# Electrical.net
KiCad netlist of a schematic drawn in EAGLE
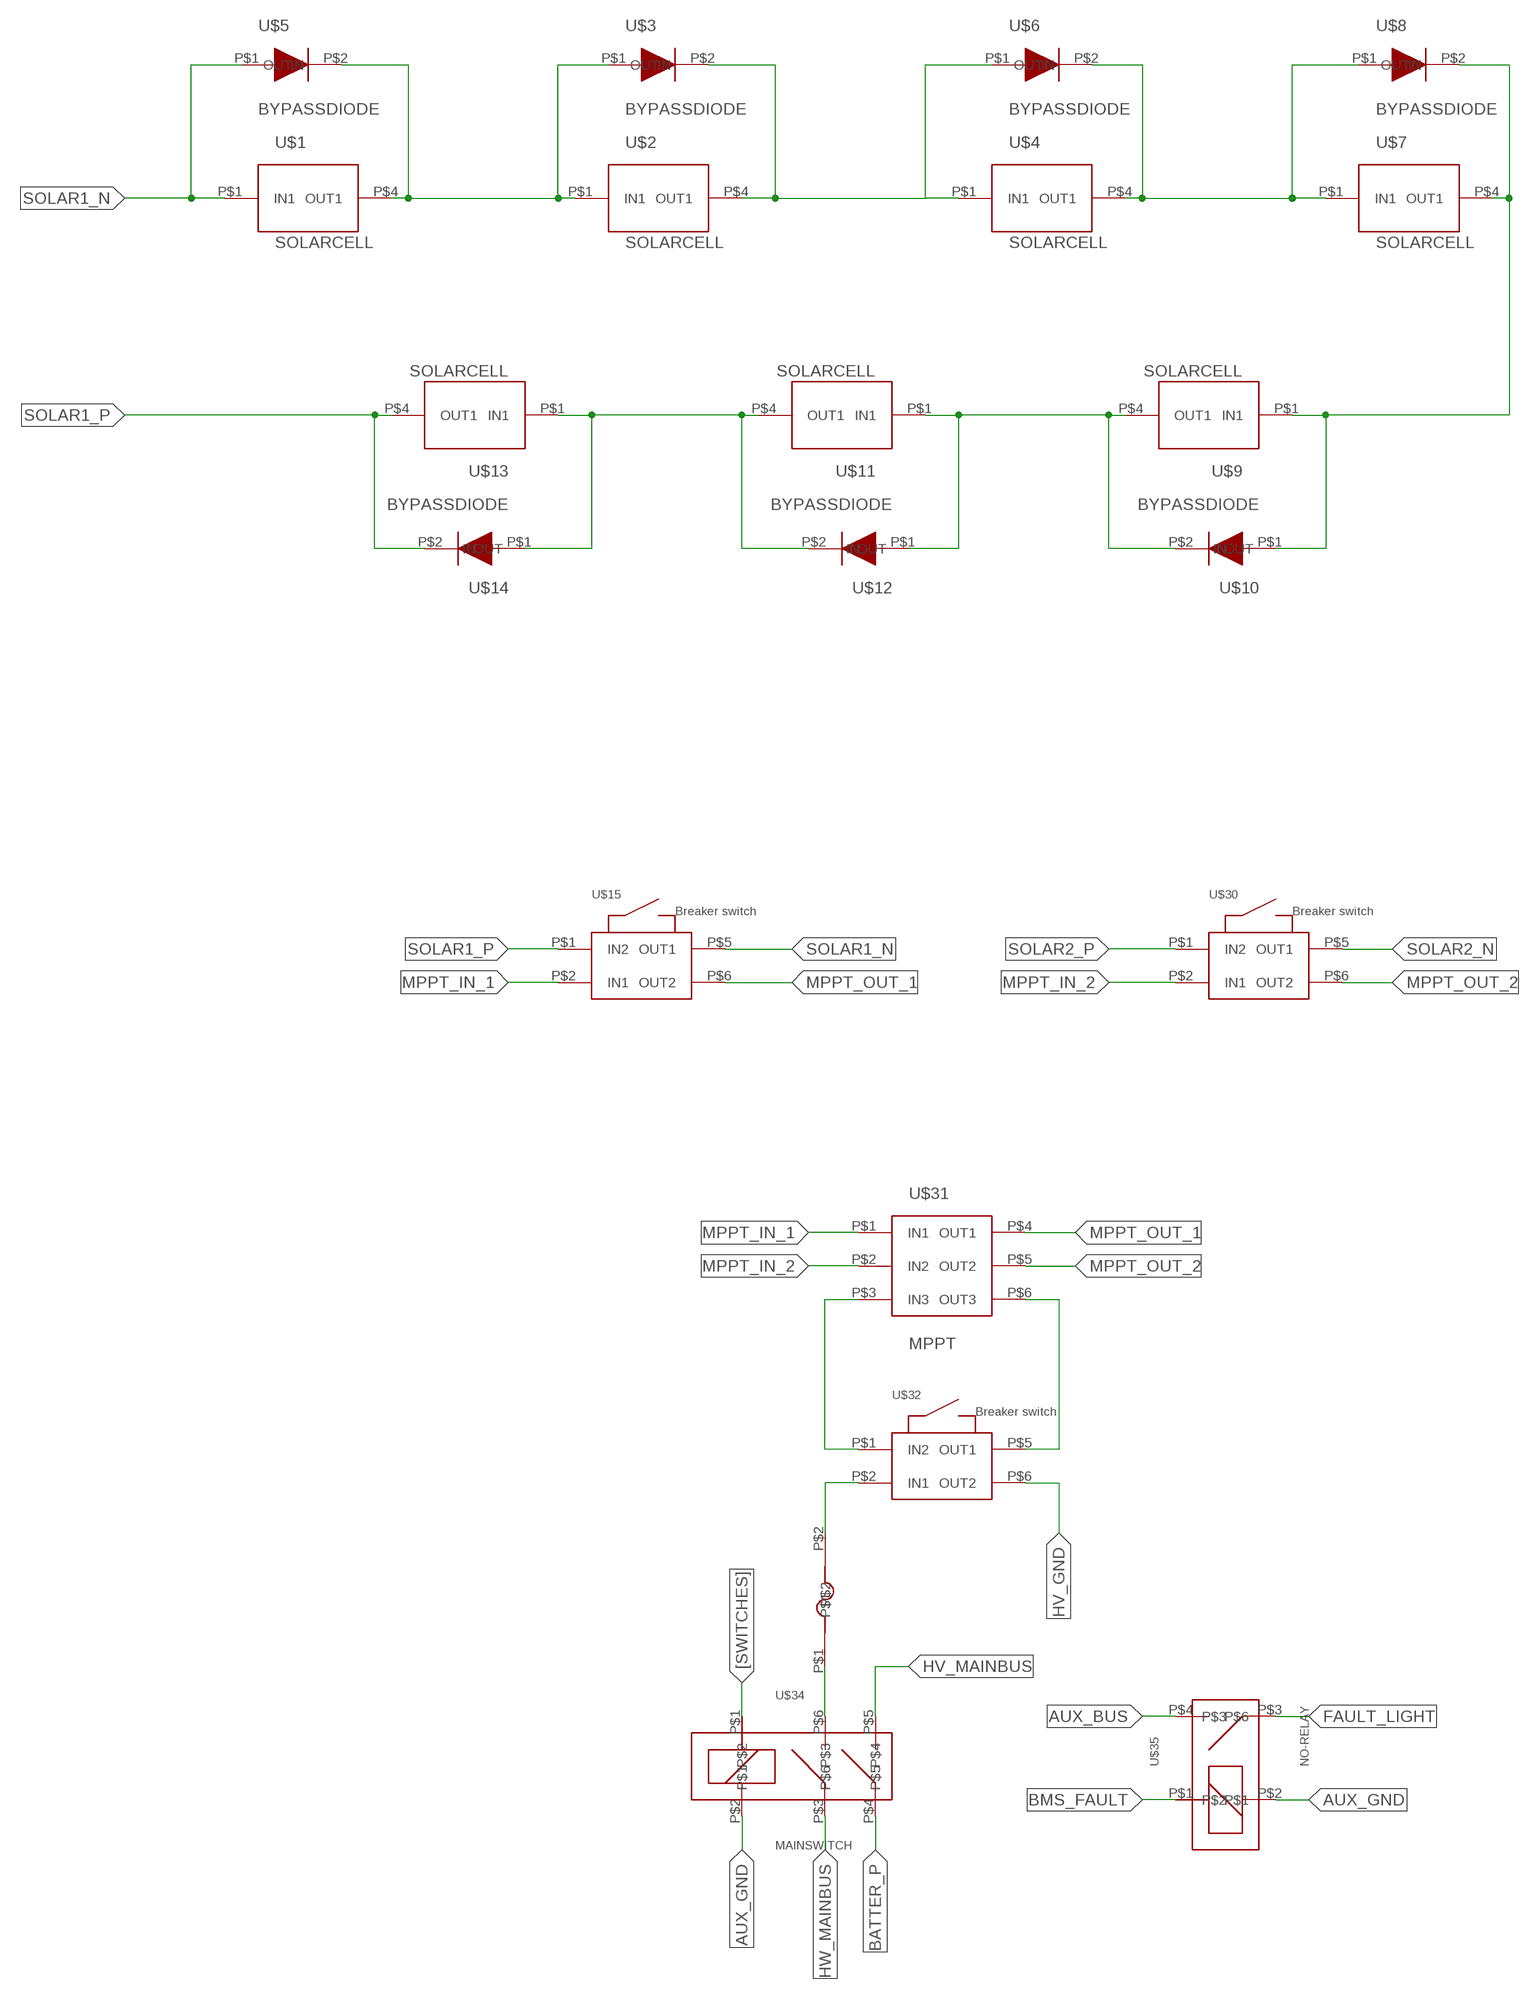
[diagram p0: schematic, sheet 1, part 1 of 3]
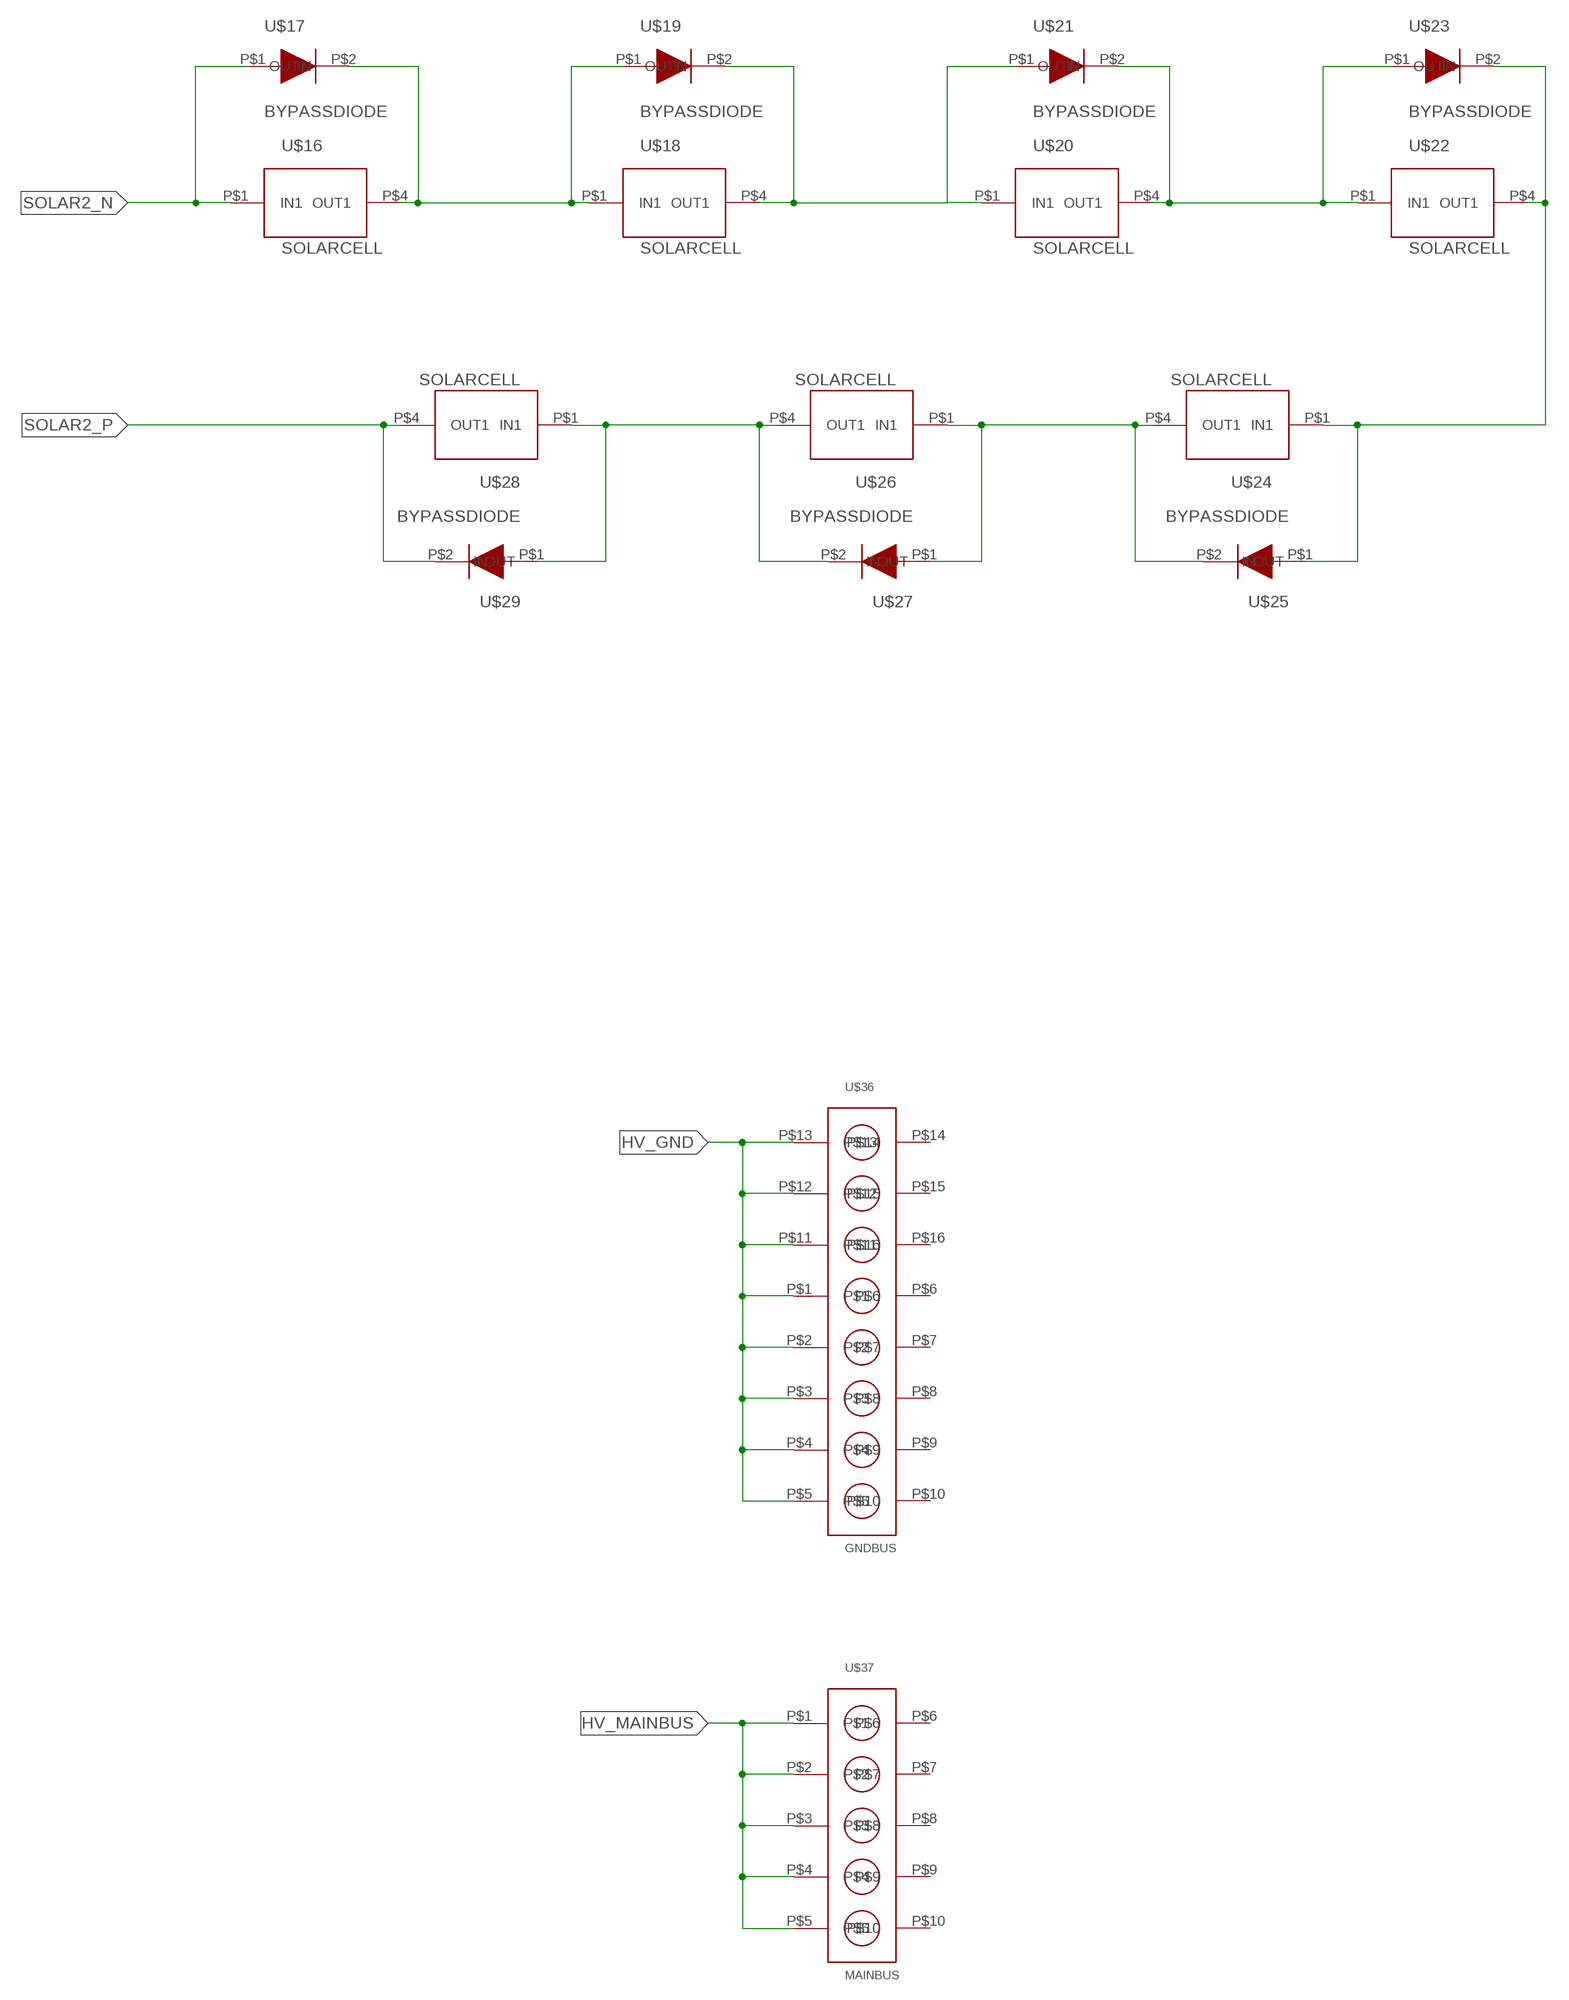
[diagram p1: schematic, sheet 1, part 2 of 3]
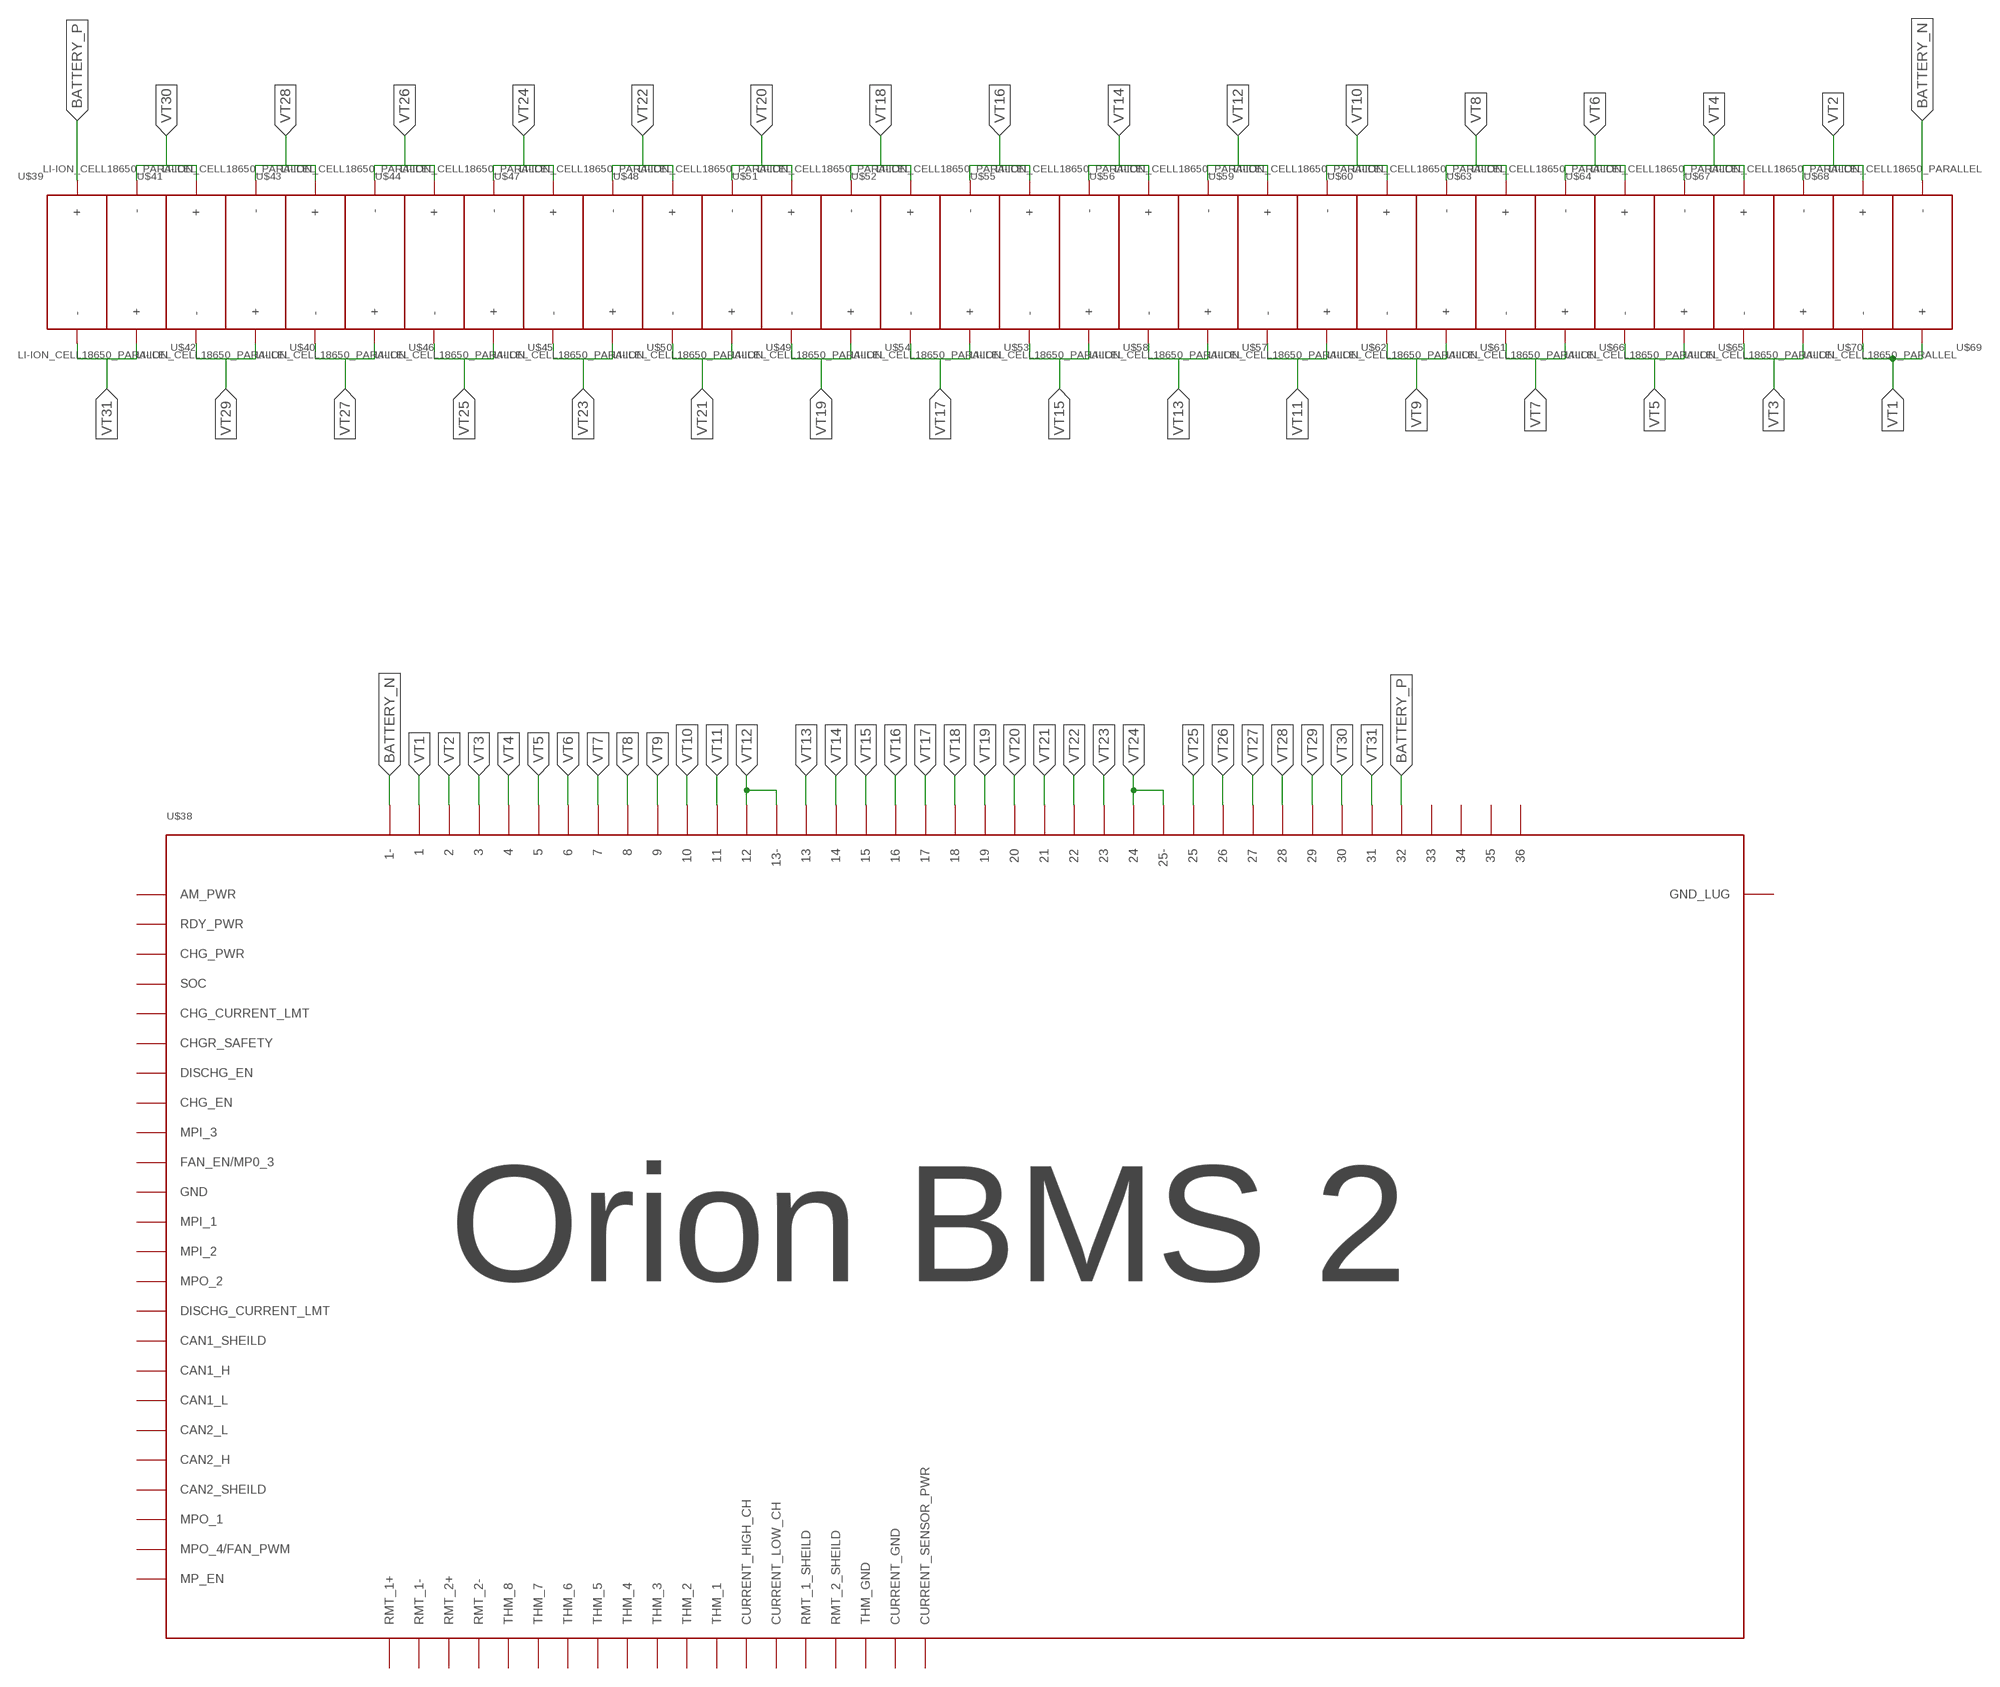
[diagram p2: schematic, sheet 1, part 3 of 3]

(export (version "E")
  (design (tool "Eeschema 10.0.6"))
  (components
    (comp (ref "U$1")
      (value "SOLARCELL")
      (footprint "eagle-import:SOLARCELL")
      (libsource (lib "eagle-import") (part "SOLARCELL"))
    )
    (comp (ref "U$2")
      (value "SOLARCELL")
      (footprint "eagle-import:SOLARCELL")
      (libsource (lib "eagle-import") (part "SOLARCELL"))
    )
    (comp (ref "U$3")
      (value "BYPASSDIODE")
      (footprint "eagle-import:BYPASSDIODE")
      (libsource (lib "eagle-import") (part "BYPASSDIODE"))
    )
    (comp (ref "U$4")
      (value "SOLARCELL")
      (footprint "eagle-import:SOLARCELL")
      (libsource (lib "eagle-import") (part "SOLARCELL"))
    )
    (comp (ref "U$5")
      (value "BYPASSDIODE")
      (footprint "eagle-import:BYPASSDIODE")
      (libsource (lib "eagle-import") (part "BYPASSDIODE"))
    )
    (comp (ref "U$6")
      (value "BYPASSDIODE")
      (footprint "eagle-import:BYPASSDIODE")
      (libsource (lib "eagle-import") (part "BYPASSDIODE"))
    )
    (comp (ref "U$7")
      (value "SOLARCELL")
      (footprint "eagle-import:SOLARCELL")
      (libsource (lib "eagle-import") (part "SOLARCELL"))
    )
    (comp (ref "U$8")
      (value "BYPASSDIODE")
      (footprint "eagle-import:BYPASSDIODE")
      (libsource (lib "eagle-import") (part "BYPASSDIODE"))
    )
    (comp (ref "U$9")
      (value "SOLARCELL")
      (footprint "eagle-import:SOLARCELL")
      (libsource (lib "eagle-import") (part "SOLARCELL"))
    )
    (comp (ref "U$10")
      (value "BYPASSDIODE")
      (footprint "eagle-import:BYPASSDIODE")
      (libsource (lib "eagle-import") (part "BYPASSDIODE"))
    )
    (comp (ref "U$11")
      (value "SOLARCELL")
      (footprint "eagle-import:SOLARCELL")
      (libsource (lib "eagle-import") (part "SOLARCELL"))
    )
    (comp (ref "U$12")
      (value "BYPASSDIODE")
      (footprint "eagle-import:BYPASSDIODE")
      (libsource (lib "eagle-import") (part "BYPASSDIODE"))
    )
    (comp (ref "U$13")
      (value "SOLARCELL")
      (footprint "eagle-import:SOLARCELL")
      (libsource (lib "eagle-import") (part "SOLARCELL"))
    )
    (comp (ref "U$14")
      (value "BYPASSDIODE")
      (footprint "eagle-import:BYPASSDIODE")
      (libsource (lib "eagle-import") (part "BYPASSDIODE"))
    )
    (comp (ref "U$15")
      (value "CIRCUITBREAKER")
      (footprint "eagle-import:CIRUITBREAKER")
      (libsource (lib "eagle-import") (part "CIRCUITBREAKER"))
    )
    (comp (ref "U$16")
      (value "SOLARCELL")
      (footprint "eagle-import:SOLARCELL")
      (libsource (lib "eagle-import") (part "SOLARCELL"))
    )
    (comp (ref "U$17")
      (value "BYPASSDIODE")
      (footprint "eagle-import:BYPASSDIODE")
      (libsource (lib "eagle-import") (part "BYPASSDIODE"))
    )
    (comp (ref "U$18")
      (value "SOLARCELL")
      (footprint "eagle-import:SOLARCELL")
      (libsource (lib "eagle-import") (part "SOLARCELL"))
    )
    (comp (ref "U$19")
      (value "BYPASSDIODE")
      (footprint "eagle-import:BYPASSDIODE")
      (libsource (lib "eagle-import") (part "BYPASSDIODE"))
    )
    (comp (ref "U$20")
      (value "SOLARCELL")
      (footprint "eagle-import:SOLARCELL")
      (libsource (lib "eagle-import") (part "SOLARCELL"))
    )
    (comp (ref "U$21")
      (value "BYPASSDIODE")
      (footprint "eagle-import:BYPASSDIODE")
      (libsource (lib "eagle-import") (part "BYPASSDIODE"))
    )
    (comp (ref "U$22")
      (value "SOLARCELL")
      (footprint "eagle-import:SOLARCELL")
      (libsource (lib "eagle-import") (part "SOLARCELL"))
    )
    (comp (ref "U$23")
      (value "BYPASSDIODE")
      (footprint "eagle-import:BYPASSDIODE")
      (libsource (lib "eagle-import") (part "BYPASSDIODE"))
    )
    (comp (ref "U$24")
      (value "SOLARCELL")
      (footprint "eagle-import:SOLARCELL")
      (libsource (lib "eagle-import") (part "SOLARCELL"))
    )
    (comp (ref "U$25")
      (value "BYPASSDIODE")
      (footprint "eagle-import:BYPASSDIODE")
      (libsource (lib "eagle-import") (part "BYPASSDIODE"))
    )
    (comp (ref "U$26")
      (value "SOLARCELL")
      (footprint "eagle-import:SOLARCELL")
      (libsource (lib "eagle-import") (part "SOLARCELL"))
    )
    (comp (ref "U$27")
      (value "BYPASSDIODE")
      (footprint "eagle-import:BYPASSDIODE")
      (libsource (lib "eagle-import") (part "BYPASSDIODE"))
    )
    (comp (ref "U$28")
      (value "SOLARCELL")
      (footprint "eagle-import:SOLARCELL")
      (libsource (lib "eagle-import") (part "SOLARCELL"))
    )
    (comp (ref "U$29")
      (value "BYPASSDIODE")
      (footprint "eagle-import:BYPASSDIODE")
      (libsource (lib "eagle-import") (part "BYPASSDIODE"))
    )
    (comp (ref "U$30")
      (value "CIRCUITBREAKER")
      (footprint "eagle-import:CIRUITBREAKER")
      (libsource (lib "eagle-import") (part "CIRCUITBREAKER"))
    )
    (comp (ref "U$31")
      (value "MPPT")
      (footprint "eagle-import:MPPT")
      (libsource (lib "eagle-import") (part "MPPT"))
    )
    (comp (ref "U$32")
      (value "CIRCUITBREAKER")
      (footprint "eagle-import:CIRUITBREAKER")
      (libsource (lib "eagle-import") (part "CIRCUITBREAKER"))
    )
    (comp (ref "U$33")
      (value "FUSE")
      (footprint "eagle-import:FUSE")
      (libsource (lib "eagle-import") (part "FUSE"))
    )
    (comp (ref "U$34")
      (value "MAINSWITCH")
      (footprint "eagle-import:MAINSWITCH")
      (libsource (lib "eagle-import") (part "MAINSWITCH"))
    )
    (comp (ref "U$35")
      (value "NO-RELAY")
      (footprint "eagle-import:NO-RELAY")
      (libsource (lib "eagle-import") (part "NO-RELAY"))
    )
    (comp (ref "U$36")
      (value "GNDBUS")
      (footprint "eagle-import:GNDBUS")
      (libsource (lib "eagle-import") (part "GNDBUS"))
    )
    (comp (ref "U$37")
      (value "MAINBUS")
      (footprint "eagle-import:MAINBUS")
      (libsource (lib "eagle-import") (part "MAINBUS"))
    )
    (comp (ref "U$38")
      (value "BMSORION_BMS_2")
      (footprint "eagle-import:GNERIC_PADS")
      (libsource (lib "eagle-import") (part "BMSORION_BMS_2"))
    )
    (comp (ref "U$39")
      (value "LI-ION_CELL18650_PARALLEL")
      (footprint "eagle-import:GNERIC_PADS")
      (libsource (lib "eagle-import") (part "LI-ION_CELL18650_PARALLEL"))
    )
    (comp (ref "U$40")
      (value "LI-ION_CELL18650_PARALLEL")
      (footprint "eagle-import:GNERIC_PADS")
      (libsource (lib "eagle-import") (part "LI-ION_CELL18650_PARALLEL"))
    )
    (comp (ref "U$41")
      (value "LI-ION_CELL18650_PARALLEL")
      (footprint "eagle-import:GNERIC_PADS")
      (libsource (lib "eagle-import") (part "LI-ION_CELL18650_PARALLEL"))
    )
    (comp (ref "U$42")
      (value "LI-ION_CELL18650_PARALLEL")
      (footprint "eagle-import:GNERIC_PADS")
      (libsource (lib "eagle-import") (part "LI-ION_CELL18650_PARALLEL"))
    )
    (comp (ref "U$43")
      (value "LI-ION_CELL18650_PARALLEL")
      (footprint "eagle-import:GNERIC_PADS")
      (libsource (lib "eagle-import") (part "LI-ION_CELL18650_PARALLEL"))
    )
    (comp (ref "U$44")
      (value "LI-ION_CELL18650_PARALLEL")
      (footprint "eagle-import:GNERIC_PADS")
      (libsource (lib "eagle-import") (part "LI-ION_CELL18650_PARALLEL"))
    )
    (comp (ref "U$45")
      (value "LI-ION_CELL18650_PARALLEL")
      (footprint "eagle-import:GNERIC_PADS")
      (libsource (lib "eagle-import") (part "LI-ION_CELL18650_PARALLEL"))
    )
    (comp (ref "U$46")
      (value "LI-ION_CELL18650_PARALLEL")
      (footprint "eagle-import:GNERIC_PADS")
      (libsource (lib "eagle-import") (part "LI-ION_CELL18650_PARALLEL"))
    )
    (comp (ref "U$47")
      (value "LI-ION_CELL18650_PARALLEL")
      (footprint "eagle-import:GNERIC_PADS")
      (libsource (lib "eagle-import") (part "LI-ION_CELL18650_PARALLEL"))
    )
    (comp (ref "U$48")
      (value "LI-ION_CELL18650_PARALLEL")
      (footprint "eagle-import:GNERIC_PADS")
      (libsource (lib "eagle-import") (part "LI-ION_CELL18650_PARALLEL"))
    )
    (comp (ref "U$49")
      (value "LI-ION_CELL18650_PARALLEL")
      (footprint "eagle-import:GNERIC_PADS")
      (libsource (lib "eagle-import") (part "LI-ION_CELL18650_PARALLEL"))
    )
    (comp (ref "U$50")
      (value "LI-ION_CELL18650_PARALLEL")
      (footprint "eagle-import:GNERIC_PADS")
      (libsource (lib "eagle-import") (part "LI-ION_CELL18650_PARALLEL"))
    )
    (comp (ref "U$51")
      (value "LI-ION_CELL18650_PARALLEL")
      (footprint "eagle-import:GNERIC_PADS")
      (libsource (lib "eagle-import") (part "LI-ION_CELL18650_PARALLEL"))
    )
    (comp (ref "U$52")
      (value "LI-ION_CELL18650_PARALLEL")
      (footprint "eagle-import:GNERIC_PADS")
      (libsource (lib "eagle-import") (part "LI-ION_CELL18650_PARALLEL"))
    )
    (comp (ref "U$53")
      (value "LI-ION_CELL18650_PARALLEL")
      (footprint "eagle-import:GNERIC_PADS")
      (libsource (lib "eagle-import") (part "LI-ION_CELL18650_PARALLEL"))
    )
    (comp (ref "U$54")
      (value "LI-ION_CELL18650_PARALLEL")
      (footprint "eagle-import:GNERIC_PADS")
      (libsource (lib "eagle-import") (part "LI-ION_CELL18650_PARALLEL"))
    )
    (comp (ref "U$55")
      (value "LI-ION_CELL18650_PARALLEL")
      (footprint "eagle-import:GNERIC_PADS")
      (libsource (lib "eagle-import") (part "LI-ION_CELL18650_PARALLEL"))
    )
    (comp (ref "U$56")
      (value "LI-ION_CELL18650_PARALLEL")
      (footprint "eagle-import:GNERIC_PADS")
      (libsource (lib "eagle-import") (part "LI-ION_CELL18650_PARALLEL"))
    )
    (comp (ref "U$57")
      (value "LI-ION_CELL18650_PARALLEL")
      (footprint "eagle-import:GNERIC_PADS")
      (libsource (lib "eagle-import") (part "LI-ION_CELL18650_PARALLEL"))
    )
    (comp (ref "U$58")
      (value "LI-ION_CELL18650_PARALLEL")
      (footprint "eagle-import:GNERIC_PADS")
      (libsource (lib "eagle-import") (part "LI-ION_CELL18650_PARALLEL"))
    )
    (comp (ref "U$59")
      (value "LI-ION_CELL18650_PARALLEL")
      (footprint "eagle-import:GNERIC_PADS")
      (libsource (lib "eagle-import") (part "LI-ION_CELL18650_PARALLEL"))
    )
    (comp (ref "U$60")
      (value "LI-ION_CELL18650_PARALLEL")
      (footprint "eagle-import:GNERIC_PADS")
      (libsource (lib "eagle-import") (part "LI-ION_CELL18650_PARALLEL"))
    )
    (comp (ref "U$61")
      (value "LI-ION_CELL18650_PARALLEL")
      (footprint "eagle-import:GNERIC_PADS")
      (libsource (lib "eagle-import") (part "LI-ION_CELL18650_PARALLEL"))
    )
    (comp (ref "U$62")
      (value "LI-ION_CELL18650_PARALLEL")
      (footprint "eagle-import:GNERIC_PADS")
      (libsource (lib "eagle-import") (part "LI-ION_CELL18650_PARALLEL"))
    )
    (comp (ref "U$63")
      (value "LI-ION_CELL18650_PARALLEL")
      (footprint "eagle-import:GNERIC_PADS")
      (libsource (lib "eagle-import") (part "LI-ION_CELL18650_PARALLEL"))
    )
    (comp (ref "U$64")
      (value "LI-ION_CELL18650_PARALLEL")
      (footprint "eagle-import:GNERIC_PADS")
      (libsource (lib "eagle-import") (part "LI-ION_CELL18650_PARALLEL"))
    )
    (comp (ref "U$65")
      (value "LI-ION_CELL18650_PARALLEL")
      (footprint "eagle-import:GNERIC_PADS")
      (libsource (lib "eagle-import") (part "LI-ION_CELL18650_PARALLEL"))
    )
    (comp (ref "U$66")
      (value "LI-ION_CELL18650_PARALLEL")
      (footprint "eagle-import:GNERIC_PADS")
      (libsource (lib "eagle-import") (part "LI-ION_CELL18650_PARALLEL"))
    )
    (comp (ref "U$67")
      (value "LI-ION_CELL18650_PARALLEL")
      (footprint "eagle-import:GNERIC_PADS")
      (libsource (lib "eagle-import") (part "LI-ION_CELL18650_PARALLEL"))
    )
    (comp (ref "U$68")
      (value "LI-ION_CELL18650_PARALLEL")
      (footprint "eagle-import:GNERIC_PADS")
      (libsource (lib "eagle-import") (part "LI-ION_CELL18650_PARALLEL"))
    )
    (comp (ref "U$69")
      (value "LI-ION_CELL18650_PARALLEL")
      (footprint "eagle-import:GNERIC_PADS")
      (libsource (lib "eagle-import") (part "LI-ION_CELL18650_PARALLEL"))
    )
    (comp (ref "U$70")
      (value "LI-ION_CELL18650_PARALLEL")
      (footprint "eagle-import:GNERIC_PADS")
      (libsource (lib "eagle-import") (part "LI-ION_CELL18650_PARALLEL"))
    )
  )
  (nets
    (net (code "1") (name "AUX_BUS") (class "Default")
      (node (ref "U$35") (pin "P$4") (pinfunction "P$6_P$4") (pintype "bidirectional"))
    )
    (net (code "2") (name "AUX_GND") (class "Default")
      (node (ref "U$34") (pin "P$2") (pinfunction "P$2_P$2") (pintype "bidirectional"))
      (node (ref "U$35") (pin "P$2") (pinfunction "P$2_P$2") (pintype "bidirectional"))
    )
    (net (code "3") (name "BATTERY_N") (class "Default")
      (node (ref "U$38") (pin "P$2") (pinfunction "1-_P$2") (pintype "bidirectional"))
      (node (ref "U$69") (pin "P$2") (pinfunction "-_P$2") (pintype "bidirectional"))
    )
    (net (code "4") (name "BATTERY_P") (class "Default")
      (node (ref "U$38") (pin "P$35") (pinfunction "32_P$35") (pintype "bidirectional"))
      (node (ref "U$39") (pin "P$1") (pinfunction "+_P$1") (pintype "bidirectional"))
    )
    (net (code "5") (name "BATTER_P") (class "Default")
      (node (ref "U$34") (pin "P$4") (pinfunction "P$4_P$4") (pintype "bidirectional"))
    )
    (net (code "6") (name "BMS_FAULT") (class "Default")
      (node (ref "U$35") (pin "P$1") (pinfunction "P$1_P$1") (pintype "bidirectional"))
    )
    (net (code "7") (name "FAULT_LIGHT") (class "Default")
      (node (ref "U$35") (pin "P$3") (pinfunction "P$3_P$3") (pintype "bidirectional"))
    )
    (net (code "8") (name "HV_GND") (class "Default")
      (node (ref "U$32") (pin "P$6") (pinfunction "OUT2_P$6") (pintype "bidirectional"))
      (node (ref "U$36") (pin "P$1") (pinfunction "P$1_P$1") (pintype "bidirectional"))
      (node (ref "U$36") (pin "P$11") (pinfunction "P$11_P$11") (pintype "bidirectional"))
      (node (ref "U$36") (pin "P$12") (pinfunction "P$12_P$12") (pintype "bidirectional"))
      (node (ref "U$36") (pin "P$13") (pinfunction "P$13_P$13") (pintype "bidirectional"))
      (node (ref "U$36") (pin "P$2") (pinfunction "P$2_P$2") (pintype "bidirectional"))
      (node (ref "U$36") (pin "P$3") (pinfunction "P$3_P$3") (pintype "bidirectional"))
      (node (ref "U$36") (pin "P$4") (pinfunction "P$4_P$4") (pintype "bidirectional"))
      (node (ref "U$36") (pin "P$5") (pinfunction "P$5_P$5") (pintype "bidirectional"))
    )
    (net (code "9") (name "HV_MAINBUS") (class "Default")
      (node (ref "U$34") (pin "P$5") (pinfunction "P$5_P$5") (pintype "bidirectional"))
      (node (ref "U$37") (pin "P$1") (pinfunction "P$1_P$1") (pintype "bidirectional"))
      (node (ref "U$37") (pin "P$2") (pinfunction "P$2_P$2") (pintype "bidirectional"))
      (node (ref "U$37") (pin "P$3") (pinfunction "P$3_P$3") (pintype "bidirectional"))
      (node (ref "U$37") (pin "P$4") (pinfunction "P$4_P$4") (pintype "bidirectional"))
      (node (ref "U$37") (pin "P$5") (pinfunction "P$5_P$5") (pintype "bidirectional"))
    )
    (net (code "10") (name "HW_MAINBUS") (class "Default")
      (node (ref "U$34") (pin "P$3") (pinfunction "P$3_P$3") (pintype "bidirectional"))
    )
    (net (code "11") (name "MPPT_IN_1") (class "Default")
      (node (ref "U$15") (pin "P$2") (pinfunction "IN1_P$2") (pintype "bidirectional"))
      (node (ref "U$31") (pin "P$1") (pinfunction "IN1_P$1") (pintype "bidirectional"))
    )
    (net (code "12") (name "MPPT_IN_2") (class "Default")
      (node (ref "U$30") (pin "P$2") (pinfunction "IN1_P$2") (pintype "bidirectional"))
      (node (ref "U$31") (pin "P$2") (pinfunction "IN2_P$2") (pintype "bidirectional"))
    )
    (net (code "13") (name "MPPT_OUT_1") (class "Default")
      (node (ref "U$15") (pin "P$6") (pinfunction "OUT2_P$6") (pintype "bidirectional"))
      (node (ref "U$31") (pin "P$4") (pinfunction "OUT1_P$4") (pintype "bidirectional"))
    )
    (net (code "14") (name "MPPT_OUT_2") (class "Default")
      (node (ref "U$30") (pin "P$6") (pinfunction "OUT2_P$6") (pintype "bidirectional"))
      (node (ref "U$31") (pin "P$5") (pinfunction "OUT2_P$5") (pintype "bidirectional"))
    )
    (net (code "15") (name "Net-(U$1-OUT1)") (class "Default")
      (node (ref "U$1") (pin "P$4") (pinfunction "OUT1_P$4") (pintype "bidirectional"))
      (node (ref "U$2") (pin "P$1") (pinfunction "IN1_P$1") (pintype "bidirectional"))
      (node (ref "U$3") (pin "P$1") (pinfunction "IN_P$1") (pintype "bidirectional"))
      (node (ref "U$5") (pin "P$2") (pinfunction "OUT_P$2") (pintype "bidirectional"))
    )
    (net (code "16") (name "Net-(U$2-OUT1)") (class "Default")
      (node (ref "U$2") (pin "P$4") (pinfunction "OUT1_P$4") (pintype "bidirectional"))
      (node (ref "U$3") (pin "P$2") (pinfunction "OUT_P$2") (pintype "bidirectional"))
      (node (ref "U$4") (pin "P$1") (pinfunction "IN1_P$1") (pintype "bidirectional"))
      (node (ref "U$6") (pin "P$1") (pinfunction "IN_P$1") (pintype "bidirectional"))
    )
    (net (code "17") (name "Net-(U$4-OUT1)") (class "Default")
      (node (ref "U$4") (pin "P$4") (pinfunction "OUT1_P$4") (pintype "bidirectional"))
      (node (ref "U$6") (pin "P$2") (pinfunction "OUT_P$2") (pintype "bidirectional"))
      (node (ref "U$7") (pin "P$1") (pinfunction "IN1_P$1") (pintype "bidirectional"))
      (node (ref "U$8") (pin "P$1") (pinfunction "IN_P$1") (pintype "bidirectional"))
    )
    (net (code "18") (name "Net-(U$10-IN)") (class "Default")
      (node (ref "U$10") (pin "P$1") (pinfunction "IN_P$1") (pintype "bidirectional"))
      (node (ref "U$7") (pin "P$4") (pinfunction "OUT1_P$4") (pintype "bidirectional"))
      (node (ref "U$8") (pin "P$2") (pinfunction "OUT_P$2") (pintype "bidirectional"))
      (node (ref "U$9") (pin "P$1") (pinfunction "IN1_P$1") (pintype "bidirectional"))
    )
    (net (code "19") (name "Net-(U$10-OUT)") (class "Default")
      (node (ref "U$10") (pin "P$2") (pinfunction "OUT_P$2") (pintype "bidirectional"))
      (node (ref "U$11") (pin "P$1") (pinfunction "IN1_P$1") (pintype "bidirectional"))
      (node (ref "U$12") (pin "P$1") (pinfunction "IN_P$1") (pintype "bidirectional"))
      (node (ref "U$9") (pin "P$4") (pinfunction "OUT1_P$4") (pintype "bidirectional"))
    )
    (net (code "20") (name "Net-(U$11-OUT1)") (class "Default")
      (node (ref "U$11") (pin "P$4") (pinfunction "OUT1_P$4") (pintype "bidirectional"))
      (node (ref "U$12") (pin "P$2") (pinfunction "OUT_P$2") (pintype "bidirectional"))
      (node (ref "U$13") (pin "P$1") (pinfunction "IN1_P$1") (pintype "bidirectional"))
      (node (ref "U$14") (pin "P$1") (pinfunction "IN_P$1") (pintype "bidirectional"))
    )
    (net (code "21") (name "Net-(U$16-OUT1)") (class "Default")
      (node (ref "U$16") (pin "P$4") (pinfunction "OUT1_P$4") (pintype "bidirectional"))
      (node (ref "U$17") (pin "P$2") (pinfunction "OUT_P$2") (pintype "bidirectional"))
      (node (ref "U$18") (pin "P$1") (pinfunction "IN1_P$1") (pintype "bidirectional"))
      (node (ref "U$19") (pin "P$1") (pinfunction "IN_P$1") (pintype "bidirectional"))
    )
    (net (code "22") (name "Net-(U$18-OUT1)") (class "Default")
      (node (ref "U$18") (pin "P$4") (pinfunction "OUT1_P$4") (pintype "bidirectional"))
      (node (ref "U$19") (pin "P$2") (pinfunction "OUT_P$2") (pintype "bidirectional"))
      (node (ref "U$20") (pin "P$1") (pinfunction "IN1_P$1") (pintype "bidirectional"))
      (node (ref "U$21") (pin "P$1") (pinfunction "IN_P$1") (pintype "bidirectional"))
    )
    (net (code "23") (name "Net-(U$20-OUT1)") (class "Default")
      (node (ref "U$20") (pin "P$4") (pinfunction "OUT1_P$4") (pintype "bidirectional"))
      (node (ref "U$21") (pin "P$2") (pinfunction "OUT_P$2") (pintype "bidirectional"))
      (node (ref "U$22") (pin "P$1") (pinfunction "IN1_P$1") (pintype "bidirectional"))
      (node (ref "U$23") (pin "P$1") (pinfunction "IN_P$1") (pintype "bidirectional"))
    )
    (net (code "24") (name "Net-(U$22-OUT1)") (class "Default")
      (node (ref "U$22") (pin "P$4") (pinfunction "OUT1_P$4") (pintype "bidirectional"))
      (node (ref "U$23") (pin "P$2") (pinfunction "OUT_P$2") (pintype "bidirectional"))
      (node (ref "U$24") (pin "P$1") (pinfunction "IN1_P$1") (pintype "bidirectional"))
      (node (ref "U$25") (pin "P$1") (pinfunction "IN_P$1") (pintype "bidirectional"))
    )
    (net (code "25") (name "Net-(U$24-OUT1)") (class "Default")
      (node (ref "U$24") (pin "P$4") (pinfunction "OUT1_P$4") (pintype "bidirectional"))
      (node (ref "U$25") (pin "P$2") (pinfunction "OUT_P$2") (pintype "bidirectional"))
      (node (ref "U$26") (pin "P$1") (pinfunction "IN1_P$1") (pintype "bidirectional"))
      (node (ref "U$27") (pin "P$1") (pinfunction "IN_P$1") (pintype "bidirectional"))
    )
    (net (code "26") (name "Net-(U$26-OUT1)") (class "Default")
      (node (ref "U$26") (pin "P$4") (pinfunction "OUT1_P$4") (pintype "bidirectional"))
      (node (ref "U$27") (pin "P$2") (pinfunction "OUT_P$2") (pintype "bidirectional"))
      (node (ref "U$28") (pin "P$1") (pinfunction "IN1_P$1") (pintype "bidirectional"))
      (node (ref "U$29") (pin "P$1") (pinfunction "IN_P$1") (pintype "bidirectional"))
    )
    (net (code "27") (name "Net-(U$31-IN3)") (class "Default")
      (node (ref "U$31") (pin "P$3") (pinfunction "IN3_P$3") (pintype "bidirectional"))
      (node (ref "U$32") (pin "P$1") (pinfunction "IN2_P$1") (pintype "bidirectional"))
    )
    (net (code "28") (name "Net-(U$31-OUT3)") (class "Default")
      (node (ref "U$31") (pin "P$6") (pinfunction "OUT3_P$6") (pintype "bidirectional"))
      (node (ref "U$32") (pin "P$5") (pinfunction "OUT1_P$5") (pintype "bidirectional"))
    )
    (net (code "29") (name "Net-(U$32-IN1)") (class "Default")
      (node (ref "U$32") (pin "P$2") (pinfunction "IN1_P$2") (pintype "bidirectional"))
      (node (ref "U$33") (pin "P$2") (pinfunction "P$2_P$2") (pintype "bidirectional"))
    )
    (net (code "30") (name "Net-(U$33-PadP$1)") (class "Default")
      (node (ref "U$33") (pin "P$1") (pinfunction "P$1_P$1") (pintype "bidirectional"))
      (node (ref "U$34") (pin "P$6") (pinfunction "P$6_P$6") (pintype "bidirectional"))
    )
    (net (code "31") (name "Net-(U$39--)") (class "Default")
      (node (ref "U$39") (pin "P$2") (pinfunction "-_P$2") (pintype "bidirectional"))
      (node (ref "U$42") (pin "P$1") (pinfunction "+_P$1") (pintype "bidirectional"))
    )
    (net (code "32") (name "Net-(U$40-+)") (class "Default")
      (node (ref "U$40") (pin "P$1") (pinfunction "+_P$1") (pintype "bidirectional"))
      (node (ref "U$41") (pin "P$2") (pinfunction "-_P$2") (pintype "bidirectional"))
    )
    (net (code "33") (name "Net-(U$40--)") (class "Default")
      (node (ref "U$40") (pin "P$2") (pinfunction "-_P$2") (pintype "bidirectional"))
      (node (ref "U$43") (pin "P$1") (pinfunction "+_P$1") (pintype "bidirectional"))
    )
    (net (code "34") (name "Net-(U$41-+)") (class "Default")
      (node (ref "U$41") (pin "P$1") (pinfunction "+_P$1") (pintype "bidirectional"))
      (node (ref "U$42") (pin "P$2") (pinfunction "-_P$2") (pintype "bidirectional"))
    )
    (net (code "35") (name "Net-(U$43--)") (class "Default")
      (node (ref "U$43") (pin "P$2") (pinfunction "-_P$2") (pintype "bidirectional"))
      (node (ref "U$46") (pin "P$1") (pinfunction "+_P$1") (pintype "bidirectional"))
    )
    (net (code "36") (name "Net-(U$44-+)") (class "Default")
      (node (ref "U$44") (pin "P$1") (pinfunction "+_P$1") (pintype "bidirectional"))
      (node (ref "U$46") (pin "P$2") (pinfunction "-_P$2") (pintype "bidirectional"))
    )
    (net (code "37") (name "Net-(U$44--)") (class "Default")
      (node (ref "U$44") (pin "P$2") (pinfunction "-_P$2") (pintype "bidirectional"))
      (node (ref "U$45") (pin "P$1") (pinfunction "+_P$1") (pintype "bidirectional"))
    )
    (net (code "38") (name "Net-(U$45--)") (class "Default")
      (node (ref "U$45") (pin "P$2") (pinfunction "-_P$2") (pintype "bidirectional"))
      (node (ref "U$47") (pin "P$1") (pinfunction "+_P$1") (pintype "bidirectional"))
    )
    (net (code "39") (name "Net-(U$47--)") (class "Default")
      (node (ref "U$47") (pin "P$2") (pinfunction "-_P$2") (pintype "bidirectional"))
      (node (ref "U$50") (pin "P$1") (pinfunction "+_P$1") (pintype "bidirectional"))
    )
    (net (code "40") (name "Net-(U$48-+)") (class "Default")
      (node (ref "U$48") (pin "P$1") (pinfunction "+_P$1") (pintype "bidirectional"))
      (node (ref "U$50") (pin "P$2") (pinfunction "-_P$2") (pintype "bidirectional"))
    )
    (net (code "41") (name "Net-(U$48--)") (class "Default")
      (node (ref "U$48") (pin "P$2") (pinfunction "-_P$2") (pintype "bidirectional"))
      (node (ref "U$49") (pin "P$1") (pinfunction "+_P$1") (pintype "bidirectional"))
    )
    (net (code "42") (name "Net-(U$49--)") (class "Default")
      (node (ref "U$49") (pin "P$2") (pinfunction "-_P$2") (pintype "bidirectional"))
      (node (ref "U$51") (pin "P$1") (pinfunction "+_P$1") (pintype "bidirectional"))
    )
    (net (code "43") (name "Net-(U$51--)") (class "Default")
      (node (ref "U$51") (pin "P$2") (pinfunction "-_P$2") (pintype "bidirectional"))
      (node (ref "U$54") (pin "P$1") (pinfunction "+_P$1") (pintype "bidirectional"))
    )
    (net (code "44") (name "Net-(U$52-+)") (class "Default")
      (node (ref "U$52") (pin "P$1") (pinfunction "+_P$1") (pintype "bidirectional"))
      (node (ref "U$54") (pin "P$2") (pinfunction "-_P$2") (pintype "bidirectional"))
    )
    (net (code "45") (name "Net-(U$52--)") (class "Default")
      (node (ref "U$52") (pin "P$2") (pinfunction "-_P$2") (pintype "bidirectional"))
      (node (ref "U$53") (pin "P$1") (pinfunction "+_P$1") (pintype "bidirectional"))
    )
    (net (code "46") (name "Net-(U$53--)") (class "Default")
      (node (ref "U$53") (pin "P$2") (pinfunction "-_P$2") (pintype "bidirectional"))
      (node (ref "U$55") (pin "P$1") (pinfunction "+_P$1") (pintype "bidirectional"))
    )
    (net (code "47") (name "Net-(U$55--)") (class "Default")
      (node (ref "U$55") (pin "P$2") (pinfunction "-_P$2") (pintype "bidirectional"))
      (node (ref "U$58") (pin "P$1") (pinfunction "+_P$1") (pintype "bidirectional"))
    )
    (net (code "48") (name "Net-(U$56-+)") (class "Default")
      (node (ref "U$56") (pin "P$1") (pinfunction "+_P$1") (pintype "bidirectional"))
      (node (ref "U$58") (pin "P$2") (pinfunction "-_P$2") (pintype "bidirectional"))
    )
    (net (code "49") (name "Net-(U$56--)") (class "Default")
      (node (ref "U$56") (pin "P$2") (pinfunction "-_P$2") (pintype "bidirectional"))
      (node (ref "U$57") (pin "P$1") (pinfunction "+_P$1") (pintype "bidirectional"))
    )
    (net (code "50") (name "Net-(U$57--)") (class "Default")
      (node (ref "U$57") (pin "P$2") (pinfunction "-_P$2") (pintype "bidirectional"))
      (node (ref "U$59") (pin "P$1") (pinfunction "+_P$1") (pintype "bidirectional"))
    )
    (net (code "51") (name "Net-(U$59--)") (class "Default")
      (node (ref "U$59") (pin "P$2") (pinfunction "-_P$2") (pintype "bidirectional"))
      (node (ref "U$62") (pin "P$1") (pinfunction "+_P$1") (pintype "bidirectional"))
    )
    (net (code "52") (name "Net-(U$60-+)") (class "Default")
      (node (ref "U$60") (pin "P$1") (pinfunction "+_P$1") (pintype "bidirectional"))
      (node (ref "U$62") (pin "P$2") (pinfunction "-_P$2") (pintype "bidirectional"))
    )
    (net (code "53") (name "Net-(U$60--)") (class "Default")
      (node (ref "U$60") (pin "P$2") (pinfunction "-_P$2") (pintype "bidirectional"))
      (node (ref "U$61") (pin "P$1") (pinfunction "+_P$1") (pintype "bidirectional"))
    )
    (net (code "54") (name "Net-(U$61--)") (class "Default")
      (node (ref "U$61") (pin "P$2") (pinfunction "-_P$2") (pintype "bidirectional"))
      (node (ref "U$63") (pin "P$1") (pinfunction "+_P$1") (pintype "bidirectional"))
    )
    (net (code "55") (name "Net-(U$63--)") (class "Default")
      (node (ref "U$63") (pin "P$2") (pinfunction "-_P$2") (pintype "bidirectional"))
      (node (ref "U$66") (pin "P$1") (pinfunction "+_P$1") (pintype "bidirectional"))
    )
    (net (code "56") (name "Net-(U$64-+)") (class "Default")
      (node (ref "U$64") (pin "P$1") (pinfunction "+_P$1") (pintype "bidirectional"))
      (node (ref "U$66") (pin "P$2") (pinfunction "-_P$2") (pintype "bidirectional"))
    )
    (net (code "57") (name "Net-(U$64--)") (class "Default")
      (node (ref "U$64") (pin "P$2") (pinfunction "-_P$2") (pintype "bidirectional"))
      (node (ref "U$65") (pin "P$1") (pinfunction "+_P$1") (pintype "bidirectional"))
    )
    (net (code "58") (name "Net-(U$65--)") (class "Default")
      (node (ref "U$65") (pin "P$2") (pinfunction "-_P$2") (pintype "bidirectional"))
      (node (ref "U$67") (pin "P$1") (pinfunction "+_P$1") (pintype "bidirectional"))
    )
    (net (code "59") (name "Net-(U$67--)") (class "Default")
      (node (ref "U$67") (pin "P$2") (pinfunction "-_P$2") (pintype "bidirectional"))
      (node (ref "U$70") (pin "P$1") (pinfunction "+_P$1") (pintype "bidirectional"))
    )
    (net (code "60") (name "Net-(U$68-+)") (class "Default")
      (node (ref "U$68") (pin "P$1") (pinfunction "+_P$1") (pintype "bidirectional"))
      (node (ref "U$70") (pin "P$2") (pinfunction "-_P$2") (pintype "bidirectional"))
    )
    (net (code "61") (name "SOLAR1_N") (class "Default")
      (node (ref "U$1") (pin "P$1") (pinfunction "IN1_P$1") (pintype "bidirectional"))
      (node (ref "U$15") (pin "P$5") (pinfunction "OUT1_P$5") (pintype "bidirectional"))
      (node (ref "U$5") (pin "P$1") (pinfunction "IN_P$1") (pintype "bidirectional"))
    )
    (net (code "62") (name "SOLAR1_P") (class "Default")
      (node (ref "U$13") (pin "P$4") (pinfunction "OUT1_P$4") (pintype "bidirectional"))
      (node (ref "U$14") (pin "P$2") (pinfunction "OUT_P$2") (pintype "bidirectional"))
      (node (ref "U$15") (pin "P$1") (pinfunction "IN2_P$1") (pintype "bidirectional"))
    )
    (net (code "63") (name "SOLAR2_N") (class "Default")
      (node (ref "U$16") (pin "P$1") (pinfunction "IN1_P$1") (pintype "bidirectional"))
      (node (ref "U$17") (pin "P$1") (pinfunction "IN_P$1") (pintype "bidirectional"))
      (node (ref "U$30") (pin "P$5") (pinfunction "OUT1_P$5") (pintype "bidirectional"))
    )
    (net (code "64") (name "SOLAR2_P") (class "Default")
      (node (ref "U$28") (pin "P$4") (pinfunction "OUT1_P$4") (pintype "bidirectional"))
      (node (ref "U$29") (pin "P$2") (pinfunction "OUT_P$2") (pintype "bidirectional"))
      (node (ref "U$30") (pin "P$1") (pinfunction "IN2_P$1") (pintype "bidirectional"))
    )
    (net (code "65") (name "VT1") (class "Default")
      (node (ref "U$38") (pin "P$1") (pinfunction "1_P$1") (pintype "bidirectional"))
      (node (ref "U$68") (pin "P$2") (pinfunction "-_P$2") (pintype "bidirectional"))
      (node (ref "U$69") (pin "P$1") (pinfunction "+_P$1") (pintype "bidirectional"))
    )
    (net (code "66") (name "VT2") (class "Default")
      (node (ref "U$38") (pin "P$3") (pinfunction "2_P$3") (pintype "bidirectional"))
    )
    (net (code "67") (name "VT3") (class "Default")
      (node (ref "U$38") (pin "P$4") (pinfunction "3_P$4") (pintype "bidirectional"))
    )
    (net (code "68") (name "VT4") (class "Default")
      (node (ref "U$38") (pin "P$5") (pinfunction "4_P$5") (pintype "bidirectional"))
    )
    (net (code "69") (name "VT5") (class "Default")
      (node (ref "U$38") (pin "P$6") (pinfunction "5_P$6") (pintype "bidirectional"))
    )
    (net (code "70") (name "VT6") (class "Default")
      (node (ref "U$38") (pin "P$7") (pinfunction "6_P$7") (pintype "bidirectional"))
    )
    (net (code "71") (name "VT7") (class "Default")
      (node (ref "U$38") (pin "P$8") (pinfunction "7_P$8") (pintype "bidirectional"))
    )
    (net (code "72") (name "VT8") (class "Default")
      (node (ref "U$38") (pin "P$9") (pinfunction "8_P$9") (pintype "bidirectional"))
    )
    (net (code "73") (name "VT9") (class "Default")
      (node (ref "U$38") (pin "P$10") (pinfunction "9_P$10") (pintype "bidirectional"))
    )
    (net (code "74") (name "VT10") (class "Default")
      (node (ref "U$38") (pin "P$11") (pinfunction "10_P$11") (pintype "bidirectional"))
    )
    (net (code "75") (name "VT11") (class "Default")
      (node (ref "U$38") (pin "P$12") (pinfunction "11_P$12") (pintype "bidirectional"))
    )
    (net (code "76") (name "VT12") (class "Default")
      (node (ref "U$38") (pin "P$13") (pinfunction "12_P$13") (pintype "bidirectional"))
      (node (ref "U$38") (pin "P$15") (pinfunction "13-_P$15") (pintype "bidirectional"))
    )
    (net (code "77") (name "VT13") (class "Default")
      (node (ref "U$38") (pin "P$14") (pinfunction "13_P$14") (pintype "bidirectional"))
    )
    (net (code "78") (name "VT14") (class "Default")
      (node (ref "U$38") (pin "P$16") (pinfunction "14_P$16") (pintype "bidirectional"))
    )
    (net (code "79") (name "VT15") (class "Default")
      (node (ref "U$38") (pin "P$17") (pinfunction "15_P$17") (pintype "bidirectional"))
    )
    (net (code "80") (name "VT16") (class "Default")
      (node (ref "U$38") (pin "P$18") (pinfunction "16_P$18") (pintype "bidirectional"))
    )
    (net (code "81") (name "VT17") (class "Default")
      (node (ref "U$38") (pin "P$19") (pinfunction "17_P$19") (pintype "bidirectional"))
    )
    (net (code "82") (name "VT18") (class "Default")
      (node (ref "U$38") (pin "P$20") (pinfunction "18_P$20") (pintype "bidirectional"))
    )
    (net (code "83") (name "VT19") (class "Default")
      (node (ref "U$38") (pin "P$21") (pinfunction "19_P$21") (pintype "bidirectional"))
    )
    (net (code "84") (name "VT20") (class "Default")
      (node (ref "U$38") (pin "P$22") (pinfunction "20_P$22") (pintype "bidirectional"))
    )
    (net (code "85") (name "VT21") (class "Default")
      (node (ref "U$38") (pin "P$23") (pinfunction "21_P$23") (pintype "bidirectional"))
    )
    (net (code "86") (name "VT22") (class "Default")
      (node (ref "U$38") (pin "P$24") (pinfunction "22_P$24") (pintype "bidirectional"))
    )
    (net (code "87") (name "VT23") (class "Default")
      (node (ref "U$38") (pin "P$25") (pinfunction "23_P$25") (pintype "bidirectional"))
    )
    (net (code "88") (name "VT24") (class "Default")
      (node (ref "U$38") (pin "P$26") (pinfunction "24_P$26") (pintype "bidirectional"))
      (node (ref "U$38") (pin "P$28") (pinfunction "25-_P$28") (pintype "bidirectional"))
    )
    (net (code "89") (name "VT25") (class "Default")
      (node (ref "U$38") (pin "P$27") (pinfunction "25_P$27") (pintype "bidirectional"))
    )
    (net (code "90") (name "VT26") (class "Default")
      (node (ref "U$38") (pin "P$29") (pinfunction "26_P$29") (pintype "bidirectional"))
    )
    (net (code "91") (name "VT27") (class "Default")
      (node (ref "U$38") (pin "P$30") (pinfunction "27_P$30") (pintype "bidirectional"))
    )
    (net (code "92") (name "VT28") (class "Default")
      (node (ref "U$38") (pin "P$31") (pinfunction "28_P$31") (pintype "bidirectional"))
    )
    (net (code "93") (name "VT29") (class "Default")
      (node (ref "U$38") (pin "P$32") (pinfunction "29_P$32") (pintype "bidirectional"))
    )
    (net (code "94") (name "VT30") (class "Default")
      (node (ref "U$38") (pin "P$33") (pinfunction "30_P$33") (pintype "bidirectional"))
    )
    (net (code "95") (name "VT31") (class "Default")
      (node (ref "U$38") (pin "P$34") (pinfunction "31_P$34") (pintype "bidirectional"))
    )
    (net (code "96") (name "[SWITCHES]") (class "Default")
      (node (ref "U$34") (pin "P$1") (pinfunction "P$1_P$1") (pintype "bidirectional"))
    )
    (net (code "97") (name "unconnected-(U$36-PadP$6)") (class "Default")
      (node (ref "U$36") (pin "P$6") (pinfunction "P$6_P$6") (pintype "bidirectional"))
    )
    (net (code "98") (name "unconnected-(U$36-PadP$7)") (class "Default")
      (node (ref "U$36") (pin "P$7") (pinfunction "P$7_P$7") (pintype "bidirectional"))
    )
    (net (code "99") (name "unconnected-(U$36-PadP$8)") (class "Default")
      (node (ref "U$36") (pin "P$8") (pinfunction "P$8_P$8") (pintype "bidirectional"))
    )
    (net (code "100") (name "unconnected-(U$36-PadP$9)") (class "Default")
      (node (ref "U$36") (pin "P$9") (pinfunction "P$9_P$9") (pintype "bidirectional"))
    )
    (net (code "101") (name "unconnected-(U$36-PadP$10)") (class "Default")
      (node (ref "U$36") (pin "P$10") (pinfunction "P$10_P$10") (pintype "bidirectional"))
    )
    (net (code "102") (name "unconnected-(U$36-PadP$14)") (class "Default")
      (node (ref "U$36") (pin "P$14") (pinfunction "P$14_P$14") (pintype "bidirectional"))
    )
    (net (code "103") (name "unconnected-(U$36-PadP$15)") (class "Default")
      (node (ref "U$36") (pin "P$15") (pinfunction "P$15_P$15") (pintype "bidirectional"))
    )
    (net (code "104") (name "unconnected-(U$36-PadP$16)") (class "Default")
      (node (ref "U$36") (pin "P$16") (pinfunction "P$16_P$16") (pintype "bidirectional"))
    )
    (net (code "105") (name "unconnected-(U$37-PadP$6)") (class "Default")
      (node (ref "U$37") (pin "P$6") (pinfunction "P$6_P$6") (pintype "bidirectional"))
    )
    (net (code "106") (name "unconnected-(U$37-PadP$7)") (class "Default")
      (node (ref "U$37") (pin "P$7") (pinfunction "P$7_P$7") (pintype "bidirectional"))
    )
    (net (code "107") (name "unconnected-(U$37-PadP$8)") (class "Default")
      (node (ref "U$37") (pin "P$8") (pinfunction "P$8_P$8") (pintype "bidirectional"))
    )
    (net (code "108") (name "unconnected-(U$37-PadP$9)") (class "Default")
      (node (ref "U$37") (pin "P$9") (pinfunction "P$9_P$9") (pintype "bidirectional"))
    )
    (net (code "109") (name "unconnected-(U$37-PadP$10)") (class "Default")
      (node (ref "U$37") (pin "P$10") (pinfunction "P$10_P$10") (pintype "bidirectional"))
    )
    (net (code "110") (name "unconnected-(U$38-33-PadP$36)") (class "Default")
      (node (ref "U$38") (pin "P$36") (pinfunction "33_P$36") (pintype "bidirectional"))
    )
    (net (code "111") (name "unconnected-(U$38-34-PadP$37)") (class "Default")
      (node (ref "U$38") (pin "P$37") (pinfunction "34_P$37") (pintype "bidirectional"))
    )
    (net (code "112") (name "unconnected-(U$38-35-PadP$38)") (class "Default")
      (node (ref "U$38") (pin "P$38") (pinfunction "35_P$38") (pintype "bidirectional"))
    )
    (net (code "113") (name "unconnected-(U$38-36-PadP$39)") (class "Default")
      (node (ref "U$38") (pin "P$39") (pinfunction "36_P$39") (pintype "bidirectional"))
    )
    (net (code "114") (name "unconnected-(U$38-AM_PWR-PadP$40)") (class "Default")
      (node (ref "U$38") (pin "P$40") (pinfunction "AM_PWR_P$40") (pintype "bidirectional"))
    )
    (net (code "115") (name "unconnected-(U$38-CAN1_H-PadP$41)") (class "Default")
      (node (ref "U$38") (pin "P$41") (pinfunction "CAN1_H_P$41") (pintype "bidirectional"))
    )
    (net (code "116") (name "unconnected-(U$38-CAN1_L-PadP$42)") (class "Default")
      (node (ref "U$38") (pin "P$42") (pinfunction "CAN1_L_P$42") (pintype "bidirectional"))
    )
    (net (code "117") (name "unconnected-(U$38-CAN1_SHEILD-PadP$43)") (class "Default")
      (node (ref "U$38") (pin "P$43") (pinfunction "CAN1_SHEILD_P$43") (pintype "bidirectional"))
    )
    (net (code "118") (name "unconnected-(U$38-CAN2_H-PadP$44)") (class "Default")
      (node (ref "U$38") (pin "P$44") (pinfunction "CAN2_H_P$44") (pintype "bidirectional"))
    )
    (net (code "119") (name "unconnected-(U$38-CAN2_L-PadP$45)") (class "Default")
      (node (ref "U$38") (pin "P$45") (pinfunction "CAN2_L_P$45") (pintype "bidirectional"))
    )
    (net (code "120") (name "unconnected-(U$38-CAN2_SHEILD-PadP$46)") (class "Default")
      (node (ref "U$38") (pin "P$46") (pinfunction "CAN2_SHEILD_P$46") (pintype "bidirectional"))
    )
    (net (code "121") (name "unconnected-(U$38-CHGR_SAFETY-PadP$47)") (class "Default")
      (node (ref "U$38") (pin "P$47") (pinfunction "CHGR_SAFETY_P$47") (pintype "bidirectional"))
    )
    (net (code "122") (name "unconnected-(U$38-CHG_CURRENT_LMT-PadP$48)") (class "Default")
      (node (ref "U$38") (pin "P$48") (pinfunction "CHG_CURRENT_LMT_P$48") (pintype "bidirectional"))
    )
    (net (code "123") (name "unconnected-(U$38-CHG_EN-PadP$49)") (class "Default")
      (node (ref "U$38") (pin "P$49") (pinfunction "CHG_EN_P$49") (pintype "bidirectional"))
    )
    (net (code "124") (name "unconnected-(U$38-CHG_PWR-PadP$50)") (class "Default")
      (node (ref "U$38") (pin "P$50") (pinfunction "CHG_PWR_P$50") (pintype "bidirectional"))
    )
    (net (code "125") (name "unconnected-(U$38-CURRENT_GND-PadP$51)") (class "Default")
      (node (ref "U$38") (pin "P$51") (pinfunction "CURRENT_GND_P$51") (pintype "bidirectional"))
    )
    (net (code "126") (name "unconnected-(U$38-CURRENT_HIGH_CH-PadP$52)") (class "Default")
      (node (ref "U$38") (pin "P$52") (pinfunction "CURRENT_HIGH_CH_P$52") (pintype "bidirectional"))
    )
    (net (code "127") (name "unconnected-(U$38-CURRENT_LOW_CH-PadP$53)") (class "Default")
      (node (ref "U$38") (pin "P$53") (pinfunction "CURRENT_LOW_CH_P$53") (pintype "bidirectional"))
    )
    (net (code "128") (name "unconnected-(U$38-CURRENT_SENSOR_PWR-PadP$54)") (class "Default")
      (node (ref "U$38") (pin "P$54") (pinfunction "CURRENT_SENSOR_PWR_P$54") (pintype "bidirectional"))
    )
    (net (code "129") (name "unconnected-(U$38-DISCHG_CURRENT_LMT-PadP$55)") (class "Default")
      (node (ref "U$38") (pin "P$55") (pinfunction "DISCHG_CURRENT_LMT_P$55") (pintype "bidirectional"))
    )
    (net (code "130") (name "unconnected-(U$38-DISCHG_EN-PadP$56)") (class "Default")
      (node (ref "U$38") (pin "P$56") (pinfunction "DISCHG_EN_P$56") (pintype "bidirectional"))
    )
    (net (code "131") (name "unconnected-(U$38-FAN_EN{slash}MP0_3-PadP$57)") (class "Default")
      (node (ref "U$38") (pin "P$57") (pinfunction "FAN_EN/MP0_3_P$57") (pintype "bidirectional"))
    )
    (net (code "132") (name "unconnected-(U$38-GND-PadP$58)") (class "Default")
      (node (ref "U$38") (pin "P$58") (pinfunction "GND_P$58") (pintype "bidirectional"))
    )
    (net (code "133") (name "unconnected-(U$38-GND_LUG-PadP$59)") (class "Default")
      (node (ref "U$38") (pin "P$59") (pinfunction "GND_LUG_P$59") (pintype "bidirectional"))
    )
    (net (code "134") (name "unconnected-(U$38-MPI_1-PadP$60)") (class "Default")
      (node (ref "U$38") (pin "P$60") (pinfunction "MPI_1_P$60") (pintype "bidirectional"))
    )
    (net (code "135") (name "unconnected-(U$38-MPI_2-PadP$61)") (class "Default")
      (node (ref "U$38") (pin "P$61") (pinfunction "MPI_2_P$61") (pintype "bidirectional"))
    )
    (net (code "136") (name "unconnected-(U$38-MPI_3-PadP$62)") (class "Default")
      (node (ref "U$38") (pin "P$62") (pinfunction "MPI_3_P$62") (pintype "bidirectional"))
    )
    (net (code "137") (name "unconnected-(U$38-MPO_1-PadP$63)") (class "Default")
      (node (ref "U$38") (pin "P$63") (pinfunction "MPO_1_P$63") (pintype "bidirectional"))
    )
    (net (code "138") (name "unconnected-(U$38-MPO_2-PadP$64)") (class "Default")
      (node (ref "U$38") (pin "P$64") (pinfunction "MPO_2_P$64") (pintype "bidirectional"))
    )
    (net (code "139") (name "unconnected-(U$38-MPO_4{slash}FAN_PWM-PadP$65)") (class "Default")
      (node (ref "U$38") (pin "P$65") (pinfunction "MPO_4/FAN_PWM_P$65") (pintype "bidirectional"))
    )
    (net (code "140") (name "unconnected-(U$38-MP_EN-PadP$66)") (class "Default")
      (node (ref "U$38") (pin "P$66") (pinfunction "MP_EN_P$66") (pintype "bidirectional"))
    )
    (net (code "141") (name "unconnected-(U$38-RDY_PWR-PadP$67)") (class "Default")
      (node (ref "U$38") (pin "P$67") (pinfunction "RDY_PWR_P$67") (pintype "bidirectional"))
    )
    (net (code "142") (name "unconnected-(U$38-RMT_1+-PadP$68)") (class "Default")
      (node (ref "U$38") (pin "P$68") (pinfunction "RMT_1+_P$68") (pintype "bidirectional"))
    )
    (net (code "143") (name "unconnected-(U$38-RMT_1--PadP$69)") (class "Default")
      (node (ref "U$38") (pin "P$69") (pinfunction "RMT_1-_P$69") (pintype "bidirectional"))
    )
    (net (code "144") (name "unconnected-(U$38-RMT_1_SHEILD-PadP$70)") (class "Default")
      (node (ref "U$38") (pin "P$70") (pinfunction "RMT_1_SHEILD_P$70") (pintype "bidirectional"))
    )
    (net (code "145") (name "unconnected-(U$38-RMT_2+-PadP$71)") (class "Default")
      (node (ref "U$38") (pin "P$71") (pinfunction "RMT_2+_P$71") (pintype "bidirectional"))
    )
    (net (code "146") (name "unconnected-(U$38-RMT_2--PadP$72)") (class "Default")
      (node (ref "U$38") (pin "P$72") (pinfunction "RMT_2-_P$72") (pintype "bidirectional"))
    )
    (net (code "147") (name "unconnected-(U$38-RMT_2_SHEILD-PadP$73)") (class "Default")
      (node (ref "U$38") (pin "P$73") (pinfunction "RMT_2_SHEILD_P$73") (pintype "bidirectional"))
    )
    (net (code "148") (name "unconnected-(U$38-SOC-PadP$74)") (class "Default")
      (node (ref "U$38") (pin "P$74") (pinfunction "SOC_P$74") (pintype "bidirectional"))
    )
    (net (code "149") (name "unconnected-(U$38-THM_1-PadP$75)") (class "Default")
      (node (ref "U$38") (pin "P$75") (pinfunction "THM_1_P$75") (pintype "bidirectional"))
    )
    (net (code "150") (name "unconnected-(U$38-THM_2-PadP$76)") (class "Default")
      (node (ref "U$38") (pin "P$76") (pinfunction "THM_2_P$76") (pintype "bidirectional"))
    )
    (net (code "151") (name "unconnected-(U$38-THM_3-PadP$77)") (class "Default")
      (node (ref "U$38") (pin "P$77") (pinfunction "THM_3_P$77") (pintype "bidirectional"))
    )
    (net (code "152") (name "unconnected-(U$38-THM_4-PadP$78)") (class "Default")
      (node (ref "U$38") (pin "P$78") (pinfunction "THM_4_P$78") (pintype "bidirectional"))
    )
    (net (code "153") (name "unconnected-(U$38-THM_5-PadP$79)") (class "Default")
      (node (ref "U$38") (pin "P$79") (pinfunction "THM_5_P$79") (pintype "bidirectional"))
    )
    (net (code "154") (name "unconnected-(U$38-THM_6-PadP$80)") (class "Default")
      (node (ref "U$38") (pin "P$80") (pinfunction "THM_6_P$80") (pintype "bidirectional"))
    )
    (net (code "155") (name "unconnected-(U$38-THM_7-PadP$81)") (class "Default")
      (node (ref "U$38") (pin "P$81") (pinfunction "THM_7_P$81") (pintype "bidirectional"))
    )
    (net (code "156") (name "unconnected-(U$38-THM_8-PadP$82)") (class "Default")
      (node (ref "U$38") (pin "P$82") (pinfunction "THM_8_P$82") (pintype "bidirectional"))
    )
    (net (code "157") (name "unconnected-(U$38-THM_GND-PadP$83)") (class "Default")
      (node (ref "U$38") (pin "P$83") (pinfunction "THM_GND_P$83") (pintype "bidirectional"))
    )
  )
)
